# audio-only-circuit.net
KiCad netlist of a schematic drawn in EAGLE
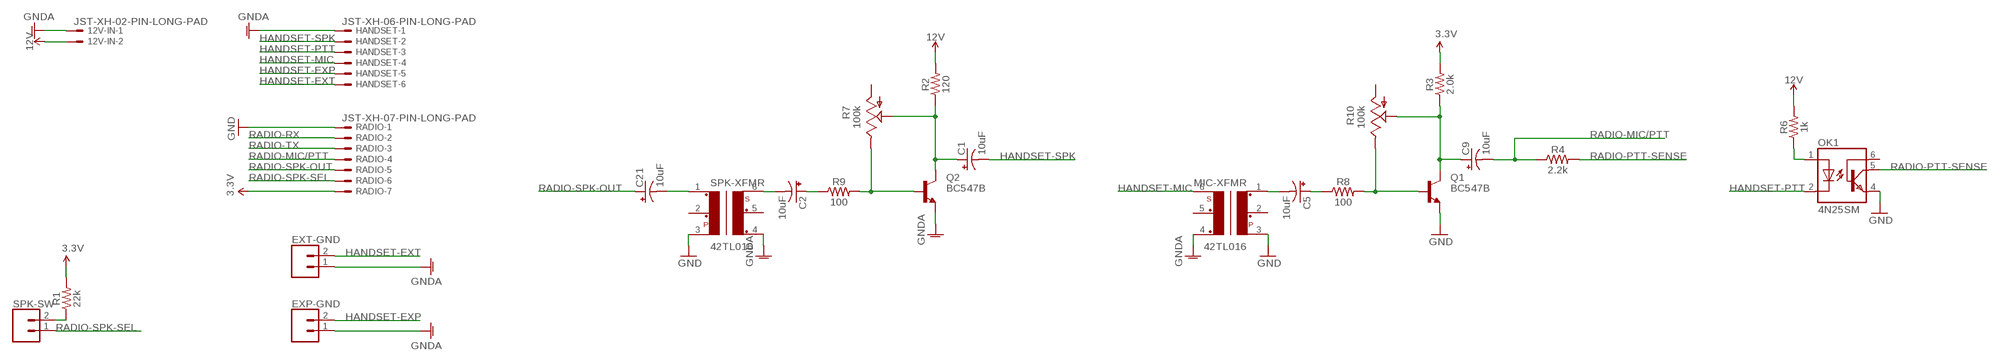
[diagram p0: schematic, sheet 1]

(export (version "E")
  (design (tool "Eeschema 10.0.6"))
  (components
    (comp (ref "12V-IN")
      (value "JST-XH-02-PIN-LONG-PAD")
      (footprint "eagle-import:JST-XH-02-PACKAGE-LONG-PAD")
      (libsource (lib "eagle-import") (part "JST-XH-02-PIN-LONG-PAD"))
    )
    (comp (ref "C1")
      (value "10uF")
      (footprint "eagle-import:E2,5-5")
      (libsource (lib "eagle-import") (part "CPOL-USE2.5-5"))
    )
    (comp (ref "C2")
      (value "10uF")
      (footprint "eagle-import:E2,5-5")
      (libsource (lib "eagle-import") (part "CPOL-USE2.5-5"))
    )
    (comp (ref "C5")
      (value "10uF")
      (footprint "eagle-import:E2,5-5")
      (libsource (lib "eagle-import") (part "CPOL-USE2.5-5"))
    )
    (comp (ref "C9")
      (value "10uF")
      (footprint "eagle-import:E2,5-5")
      (libsource (lib "eagle-import") (part "CPOL-USE2.5-5"))
    )
    (comp (ref "C21")
      (value "10uF")
      (footprint "eagle-import:E2,5-5")
      (libsource (lib "eagle-import") (part "CPOL-USE2.5-5"))
    )
    (comp (ref "EXP-GND")
      (value "CONN_02")
      (footprint "eagle-import:1X02")
      (libsource (lib "eagle-import") (part "CONN_02"))
    )
    (comp (ref "EXT-GND")
      (value "CONN_02")
      (footprint "eagle-import:1X02")
      (libsource (lib "eagle-import") (part "CONN_02"))
    )
    (comp (ref "HANDSET")
      (value "JST-XH-06-PIN-LONG-PAD")
      (footprint "eagle-import:JST-XH-06-PACKAGE-LONG-PAD")
      (libsource (lib "eagle-import") (part "JST-XH-06-PIN-LONG-PAD"))
    )
    (comp (ref "MIC-XFMR")
      (value "42TL016")
      (footprint "eagle-import:42TL")
      (libsource (lib "eagle-import") (part "42T?L016"))
    )
    (comp (ref "OK1")
      (value "4N25SM")
      (footprint "eagle-import:DIL6-SMD")
      (fields (field (name "MF") "FAIRCHILD SEMICONDUCTOR"))
      (libsource (lib "eagle-import") (part "4N?MS25"))
    )
    (comp (ref "Q1")
      (value "BC547B")
      (footprint "eagle-import:TO92")
      (libsource (lib "eagle-import") (part "BC547B"))
    )
    (comp (ref "Q2")
      (value "BC547B")
      (footprint "eagle-import:TO92")
      (libsource (lib "eagle-import") (part "BC547B"))
    )
    (comp (ref "R1")
      (value "22k")
      (footprint "eagle-import:0603")
      (libsource (lib "eagle-import") (part "22KOHM-0603-1/10W-1%"))
    )
    (comp (ref "R2")
      (value "120")
      (footprint "eagle-import:0603")
      (libsource (lib "eagle-import") (part "RESISTOR0603"))
    )
    (comp (ref "R3")
      (value "2.0k")
      (footprint "eagle-import:0603")
      (libsource (lib "eagle-import") (part "2.0KOHM-0603-1/10W-5%"))
    )
    (comp (ref "R4")
      (value "2.2k")
      (footprint "eagle-import:0603")
      (libsource (lib "eagle-import") (part "2.2KOHM-0603-1/10W-1%"))
    )
    (comp (ref "R6")
      (value "1k")
      (footprint "eagle-import:0603")
      (libsource (lib "eagle-import") (part "1KOHM-0603-1/10W-1%"))
    )
    (comp (ref "R7")
      (value "100k")
      (footprint "eagle-import:S64W")
      (libsource (lib "eagle-import") (part "TRIM_US-S64W"))
    )
    (comp (ref "R8")
      (value "100")
      (footprint "eagle-import:0603")
      (libsource (lib "eagle-import") (part "100OHM-0603-1/4W-5%"))
    )
    (comp (ref "R9")
      (value "100")
      (footprint "eagle-import:0603")
      (libsource (lib "eagle-import") (part "100OHM-0603-1/4W-5%"))
    )
    (comp (ref "R10")
      (value "100k")
      (footprint "eagle-import:S64W")
      (libsource (lib "eagle-import") (part "TRIM_US-S64W"))
    )
    (comp (ref "RADIO")
      (value "JST-XH-07-PIN-LONG-PAD")
      (footprint "eagle-import:JST-XH-07-PACKAGE-LONG-PAD")
      (libsource (lib "eagle-import") (part "JST-XH-07-PIN-LONG-PAD"))
    )
    (comp (ref "SPK-SW")
      (value "CONN_02")
      (footprint "eagle-import:1X02")
      (libsource (lib "eagle-import") (part "CONN_02"))
    )
    (comp (ref "SPK-XFMR")
      (value "42TL016")
      (footprint "eagle-import:42TL")
      (libsource (lib "eagle-import") (part "42T?L016"))
    )
  )
  (nets
    (net (code "1") (name "/HANDSET-EXP") (class "Default")
      (node (ref "EXP-GND") (pin "2") (pinfunction "2_2") (pintype "passive"))
      (node (ref "HANDSET") (pin "5") (pinfunction "S_5") (pintype "passive"))
    )
    (net (code "2") (name "/HANDSET-EXT") (class "Default")
      (node (ref "EXT-GND") (pin "2") (pinfunction "2_2") (pintype "passive"))
      (node (ref "HANDSET") (pin "6") (pinfunction "S_6") (pintype "passive"))
    )
    (net (code "3") (name "/HANDSET-MIC") (class "Default")
      (node (ref "HANDSET") (pin "4") (pinfunction "S_4") (pintype "passive"))
      (node (ref "MIC-XFMR") (pin "6") (pinfunction "6_6") (pintype "passive"))
    )
    (net (code "4") (name "/HANDSET-PTT") (class "Default")
      (node (ref "HANDSET") (pin "3") (pinfunction "S_3") (pintype "passive"))
      (node (ref "OK1") (pin "2") (pinfunction "C_2") (pintype "passive"))
    )
    (net (code "5") (name "/HANDSET-SPK") (class "Default")
      (node (ref "C1") (pin "-") (pinfunction "-_-") (pintype "passive"))
      (node (ref "HANDSET") (pin "2") (pinfunction "S_2") (pintype "passive"))
    )
    (net (code "6") (name "/RADIO-MIC{slash}PTT") (class "Default")
      (node (ref "C9") (pin "-") (pinfunction "-_-") (pintype "passive"))
      (node (ref "R4") (pin "1") (pinfunction "1_1") (pintype "passive"))
      (node (ref "RADIO") (pin "4") (pinfunction "S_4") (pintype "passive"))
    )
    (net (code "7") (name "/RADIO-PTT-SENSE") (class "Default")
      (node (ref "OK1") (pin "5") (pinfunction "COL_5") (pintype "passive"))
      (node (ref "R4") (pin "2") (pinfunction "2_2") (pintype "passive"))
    )
    (net (code "8") (name "/RADIO-RX") (class "Default")
      (node (ref "RADIO") (pin "2") (pinfunction "S_2") (pintype "passive"))
    )
    (net (code "9") (name "/RADIO-SPK-OUT") (class "Default")
      (node (ref "C21") (pin "+") (pinfunction "+_+") (pintype "passive"))
      (node (ref "RADIO") (pin "5") (pinfunction "S_5") (pintype "passive"))
    )
    (net (code "10") (name "/RADIO-SPK-SEL") (class "Default")
      (node (ref "RADIO") (pin "6") (pinfunction "S_6") (pintype "passive"))
      (node (ref "SPK-SW") (pin "1") (pinfunction "1_1") (pintype "passive"))
    )
    (net (code "11") (name "/RADIO-TX") (class "Default")
      (node (ref "RADIO") (pin "3") (pinfunction "S_3") (pintype "passive"))
    )
    (net (code "12") (name "3.3V") (class "Default")
      (node (ref "R1") (pin "2") (pinfunction "2_2") (pintype "passive"))
      (node (ref "R3") (pin "2") (pinfunction "2_2") (pintype "passive"))
      (node (ref "RADIO") (pin "7") (pinfunction "S_7") (pintype "passive"))
    )
    (net (code "13") (name "12V") (class "Default")
      (node (ref "12V-IN") (pin "2") (pinfunction "S_2") (pintype "passive"))
      (node (ref "R2") (pin "2") (pinfunction "2_2") (pintype "passive"))
      (node (ref "R6") (pin "2") (pinfunction "2_2") (pintype "passive"))
    )
    (net (code "14") (name "GND") (class "Default")
      (node (ref "MIC-XFMR") (pin "3") (pinfunction "3_3") (pintype "passive"))
      (node (ref "OK1") (pin "4") (pinfunction "EMI_4") (pintype "passive"))
      (node (ref "Q1") (pin "1") (pinfunction "E_1") (pintype "passive"))
      (node (ref "RADIO") (pin "1") (pinfunction "S_1") (pintype "passive"))
      (node (ref "SPK-XFMR") (pin "3") (pinfunction "3_3") (pintype "passive"))
    )
    (net (code "15") (name "GNDA") (class "Default")
      (node (ref "12V-IN") (pin "1") (pinfunction "S_1") (pintype "passive"))
      (node (ref "EXP-GND") (pin "1") (pinfunction "1_1") (pintype "passive"))
      (node (ref "EXT-GND") (pin "1") (pinfunction "1_1") (pintype "passive"))
      (node (ref "HANDSET") (pin "1") (pinfunction "S_1") (pintype "passive"))
      (node (ref "MIC-XFMR") (pin "4") (pinfunction "4_4") (pintype "passive"))
      (node (ref "Q2") (pin "1") (pinfunction "E_1") (pintype "passive"))
      (node (ref "SPK-XFMR") (pin "4") (pinfunction "4_4") (pintype "passive"))
    )
    (net (code "16") (name "Net-(C2-Pad+)") (class "Default")
      (node (ref "C2") (pin "+") (pinfunction "+_+") (pintype "passive"))
      (node (ref "R9") (pin "1") (pinfunction "1_1") (pintype "passive"))
    )
    (net (code "17") (name "Net-(C2-Pad-)") (class "Default")
      (node (ref "C2") (pin "-") (pinfunction "-_-") (pintype "passive"))
      (node (ref "SPK-XFMR") (pin "6") (pinfunction "6_6") (pintype "passive"))
    )
    (net (code "18") (name "Net-(C5-Pad+)") (class "Default")
      (node (ref "C5") (pin "+") (pinfunction "+_+") (pintype "passive"))
      (node (ref "R8") (pin "1") (pinfunction "1_1") (pintype "passive"))
    )
    (net (code "19") (name "Net-(C5-Pad-)") (class "Default")
      (node (ref "C5") (pin "-") (pinfunction "-_-") (pintype "passive"))
      (node (ref "MIC-XFMR") (pin "1") (pinfunction "1_1") (pintype "passive"))
    )
    (net (code "20") (name "Net-(C21-Pad-)") (class "Default")
      (node (ref "C21") (pin "-") (pinfunction "-_-") (pintype "passive"))
      (node (ref "SPK-XFMR") (pin "1") (pinfunction "1_1") (pintype "passive"))
    )
    (net (code "21") (name "Net-(OK1-A)") (class "Default")
      (node (ref "OK1") (pin "1") (pinfunction "A_1") (pintype "passive"))
      (node (ref "R6") (pin "1") (pinfunction "1_1") (pintype "passive"))
    )
    (net (code "22") (name "Net-(Q1-B)") (class "Default")
      (node (ref "Q1") (pin "2") (pinfunction "B_2") (pintype "passive"))
      (node (ref "R10") (pin "E") (pinfunction "E_E") (pintype "passive"))
      (node (ref "R8") (pin "2") (pinfunction "2_2") (pintype "passive"))
    )
    (net (code "23") (name "Net-(Q1-C)") (class "Default")
      (node (ref "C9") (pin "+") (pinfunction "+_+") (pintype "passive"))
      (node (ref "Q1") (pin "3") (pinfunction "C_3") (pintype "passive"))
      (node (ref "R10") (pin "S") (pinfunction "S_S") (pintype "passive"))
      (node (ref "R3") (pin "1") (pinfunction "1_1") (pintype "passive"))
    )
    (net (code "24") (name "Net-(Q2-B)") (class "Default")
      (node (ref "Q2") (pin "2") (pinfunction "B_2") (pintype "passive"))
      (node (ref "R7") (pin "E") (pinfunction "E_E") (pintype "passive"))
      (node (ref "R9") (pin "2") (pinfunction "2_2") (pintype "passive"))
    )
    (net (code "25") (name "Net-(Q2-C)") (class "Default")
      (node (ref "C1") (pin "+") (pinfunction "+_+") (pintype "passive"))
      (node (ref "Q2") (pin "3") (pinfunction "C_3") (pintype "passive"))
      (node (ref "R2") (pin "1") (pinfunction "1_1") (pintype "passive"))
      (node (ref "R7") (pin "S") (pinfunction "S_S") (pintype "passive"))
    )
    (net (code "26") (name "Net-(R1-Pad1)") (class "Default")
      (node (ref "R1") (pin "1") (pinfunction "1_1") (pintype "passive"))
      (node (ref "SPK-SW") (pin "2") (pinfunction "2_2") (pintype "passive"))
    )
    (net (code "27") (name "unconnected-(MIC-XFMR-Pad2)") (class "Default")
      (node (ref "MIC-XFMR") (pin "2") (pinfunction "2_2") (pintype "passive"))
    )
    (net (code "28") (name "unconnected-(MIC-XFMR-Pad5)") (class "Default")
      (node (ref "MIC-XFMR") (pin "5") (pinfunction "5_5") (pintype "passive"))
    )
    (net (code "29") (name "unconnected-(OK1-BAS-Pad6)") (class "Default")
      (node (ref "OK1") (pin "6") (pinfunction "BAS_6") (pintype "passive"))
    )
    (net (code "30") (name "unconnected-(R7-PadA)") (class "Default")
      (node (ref "R7") (pin "A") (pinfunction "A_A") (pintype "passive"))
    )
    (net (code "31") (name "unconnected-(R10-PadA)") (class "Default")
      (node (ref "R10") (pin "A") (pinfunction "A_A") (pintype "passive"))
    )
    (net (code "32") (name "unconnected-(SPK-XFMR-Pad2)") (class "Default")
      (node (ref "SPK-XFMR") (pin "2") (pinfunction "2_2") (pintype "passive"))
    )
    (net (code "33") (name "unconnected-(SPK-XFMR-Pad5)") (class "Default")
      (node (ref "SPK-XFMR") (pin "5") (pinfunction "5_5") (pintype "passive"))
    )
  )
)
